# Teensy_Board_Connectors.net
KiCad netlist of a schematic drawn in EAGLE
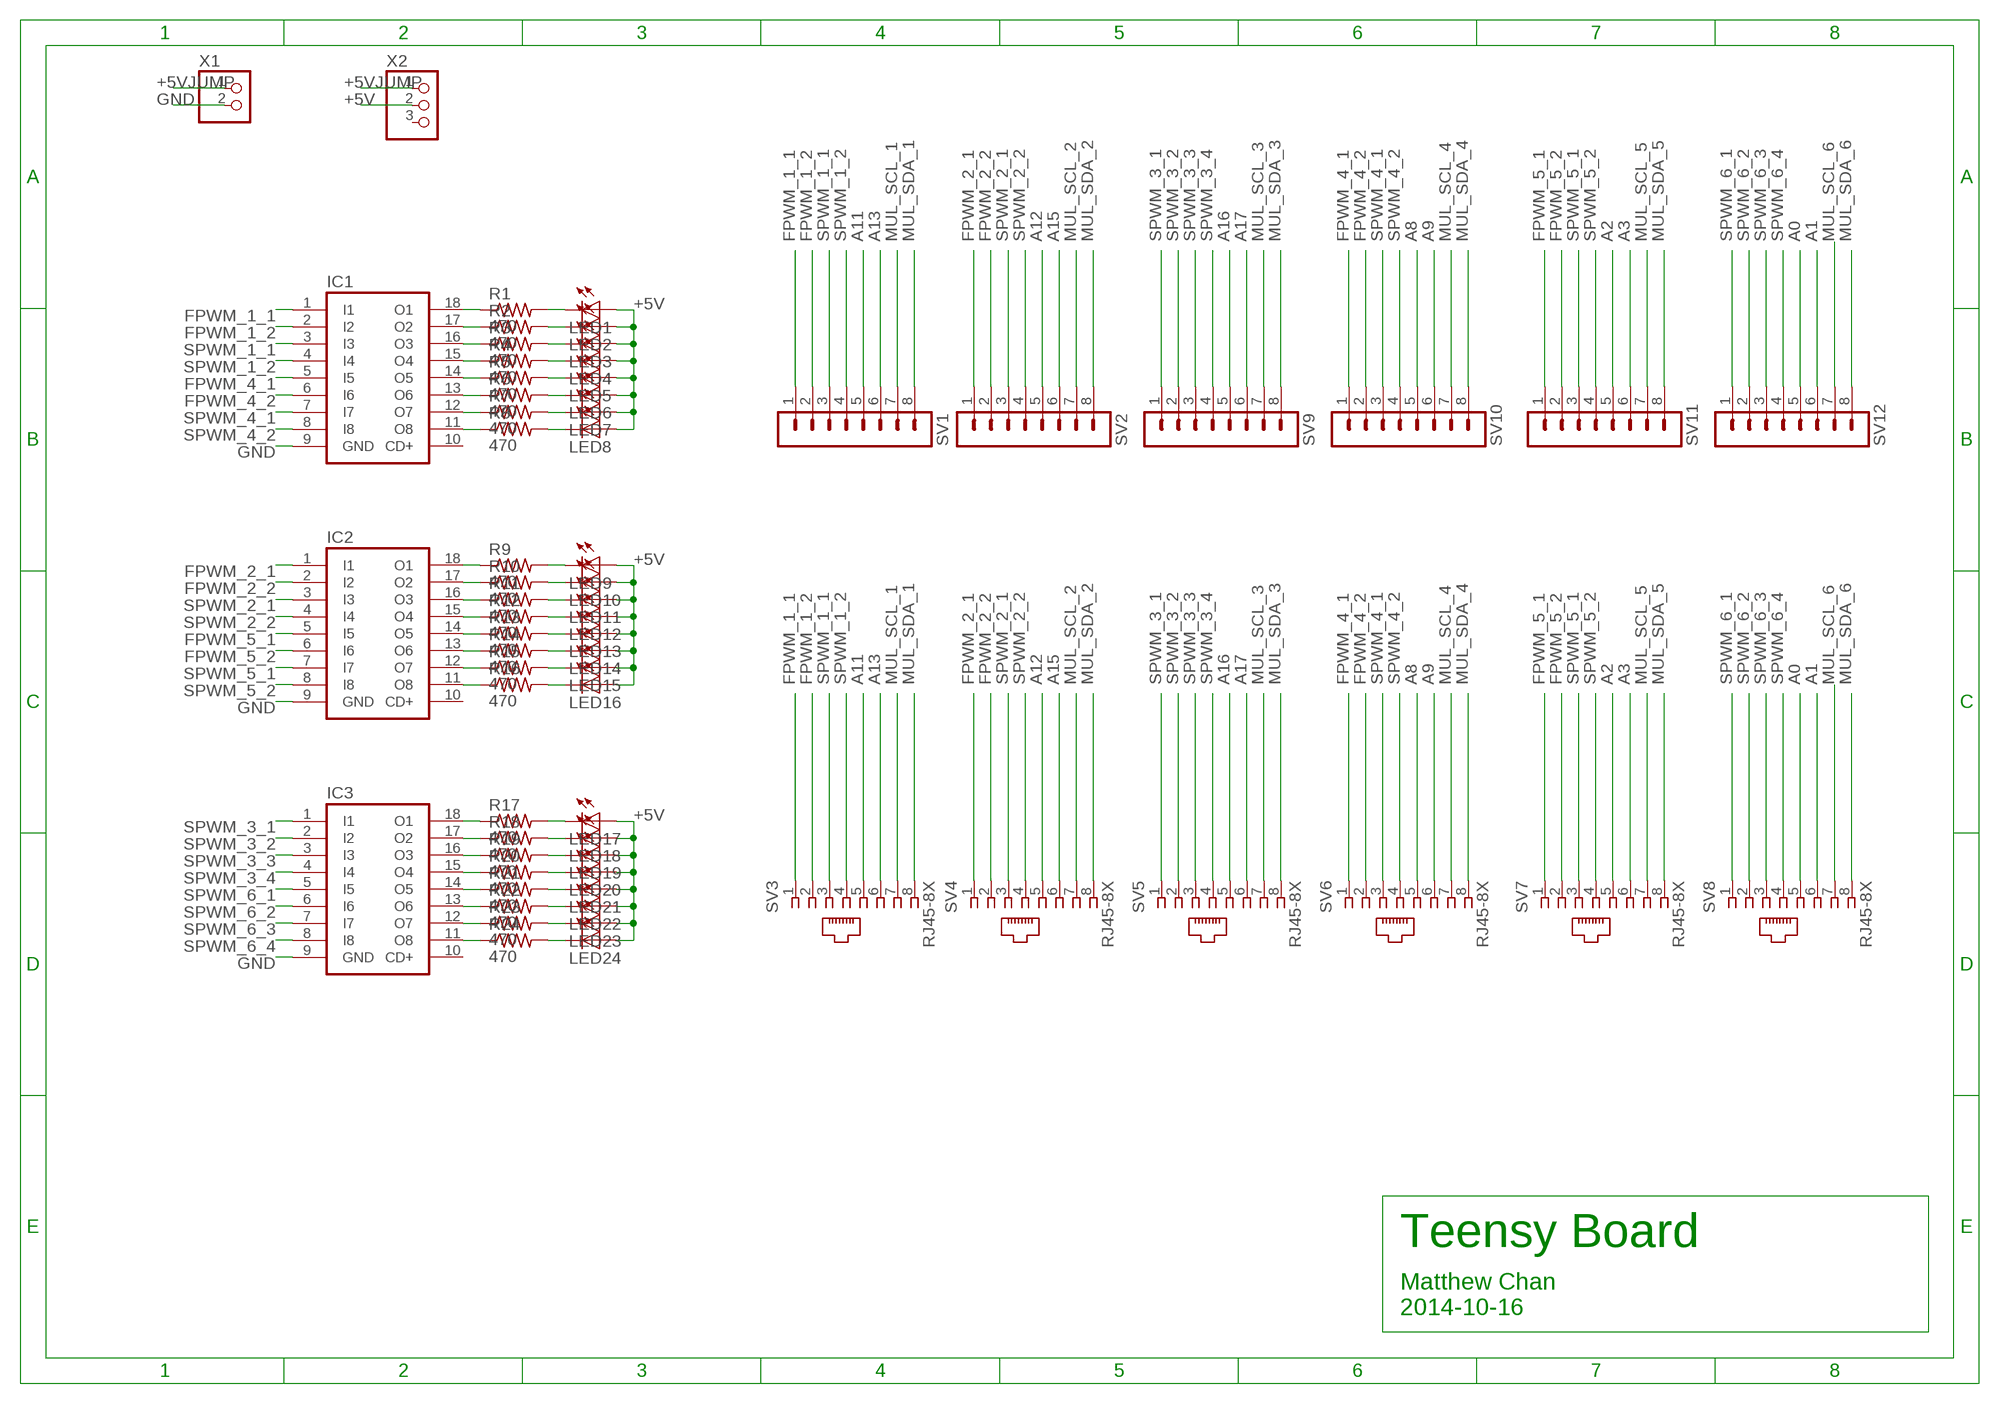
[diagram p0: schematic, sheet 1]

(export (version "E")
  (design (tool "Eeschema 10.0.6"))
  (components
    (comp (ref "IC1")
      (value "ULN2803AFWG")
      (footprint "eagle-import:SOP18")
      (libsource (lib "eagle-import") (part "ULN2803AFWG"))
    )
    (comp (ref "IC2")
      (value "ULN2803AFWG")
      (footprint "eagle-import:SOP18")
      (libsource (lib "eagle-import") (part "ULN2803AFWG"))
    )
    (comp (ref "IC3")
      (value "ULN2803AFWG")
      (footprint "eagle-import:SOP18")
      (libsource (lib "eagle-import") (part "ULN2803AFWG"))
    )
    (comp (ref "LED1")
      (value "LEDSML1206")
      (footprint "eagle-import:SML1206")
      (libsource (lib "eagle-import") (part "LEDSML1206"))
    )
    (comp (ref "LED2")
      (value "LEDSML1206")
      (footprint "eagle-import:SML1206")
      (libsource (lib "eagle-import") (part "LEDSML1206"))
    )
    (comp (ref "LED3")
      (value "LEDSML1206")
      (footprint "eagle-import:SML1206")
      (libsource (lib "eagle-import") (part "LEDSML1206"))
    )
    (comp (ref "LED4")
      (value "LEDSML1206")
      (footprint "eagle-import:SML1206")
      (libsource (lib "eagle-import") (part "LEDSML1206"))
    )
    (comp (ref "LED5")
      (value "LEDSML1206")
      (footprint "eagle-import:SML1206")
      (libsource (lib "eagle-import") (part "LEDSML1206"))
    )
    (comp (ref "LED6")
      (value "LEDSML1206")
      (footprint "eagle-import:SML1206")
      (libsource (lib "eagle-import") (part "LEDSML1206"))
    )
    (comp (ref "LED7")
      (value "LEDSML1206")
      (footprint "eagle-import:SML1206")
      (libsource (lib "eagle-import") (part "LEDSML1206"))
    )
    (comp (ref "LED8")
      (value "LEDSML1206")
      (footprint "eagle-import:SML1206")
      (libsource (lib "eagle-import") (part "LEDSML1206"))
    )
    (comp (ref "LED9")
      (value "LEDSML1206")
      (footprint "eagle-import:SML1206")
      (libsource (lib "eagle-import") (part "LEDSML1206"))
    )
    (comp (ref "LED10")
      (value "LEDSML1206")
      (footprint "eagle-import:SML1206")
      (libsource (lib "eagle-import") (part "LEDSML1206"))
    )
    (comp (ref "LED11")
      (value "LEDSML1206")
      (footprint "eagle-import:SML1206")
      (libsource (lib "eagle-import") (part "LEDSML1206"))
    )
    (comp (ref "LED12")
      (value "LEDSML1206")
      (footprint "eagle-import:SML1206")
      (libsource (lib "eagle-import") (part "LEDSML1206"))
    )
    (comp (ref "LED13")
      (value "LEDSML1206")
      (footprint "eagle-import:SML1206")
      (libsource (lib "eagle-import") (part "LEDSML1206"))
    )
    (comp (ref "LED14")
      (value "LEDSML1206")
      (footprint "eagle-import:SML1206")
      (libsource (lib "eagle-import") (part "LEDSML1206"))
    )
    (comp (ref "LED15")
      (value "LEDSML1206")
      (footprint "eagle-import:SML1206")
      (libsource (lib "eagle-import") (part "LEDSML1206"))
    )
    (comp (ref "LED16")
      (value "LEDSML1206")
      (footprint "eagle-import:SML1206")
      (libsource (lib "eagle-import") (part "LEDSML1206"))
    )
    (comp (ref "LED17")
      (value "LEDSML1206")
      (footprint "eagle-import:SML1206")
      (libsource (lib "eagle-import") (part "LEDSML1206"))
    )
    (comp (ref "LED18")
      (value "LEDSML1206")
      (footprint "eagle-import:SML1206")
      (libsource (lib "eagle-import") (part "LEDSML1206"))
    )
    (comp (ref "LED19")
      (value "LEDSML1206")
      (footprint "eagle-import:SML1206")
      (libsource (lib "eagle-import") (part "LEDSML1206"))
    )
    (comp (ref "LED20")
      (value "LEDSML1206")
      (footprint "eagle-import:SML1206")
      (libsource (lib "eagle-import") (part "LEDSML1206"))
    )
    (comp (ref "LED21")
      (value "LEDSML1206")
      (footprint "eagle-import:SML1206")
      (libsource (lib "eagle-import") (part "LEDSML1206"))
    )
    (comp (ref "LED22")
      (value "LEDSML1206")
      (footprint "eagle-import:SML1206")
      (libsource (lib "eagle-import") (part "LEDSML1206"))
    )
    (comp (ref "LED23")
      (value "LEDSML1206")
      (footprint "eagle-import:SML1206")
      (libsource (lib "eagle-import") (part "LEDSML1206"))
    )
    (comp (ref "LED24")
      (value "LEDSML1206")
      (footprint "eagle-import:SML1206")
      (libsource (lib "eagle-import") (part "LEDSML1206"))
    )
    (comp (ref "R1")
      (value "470")
      (footprint "eagle-import:R0603")
      (libsource (lib "eagle-import") (part "R-US_R0603"))
    )
    (comp (ref "R2")
      (value "470")
      (footprint "eagle-import:R0603")
      (libsource (lib "eagle-import") (part "R-US_R0603"))
    )
    (comp (ref "R3")
      (value "470")
      (footprint "eagle-import:R0603")
      (libsource (lib "eagle-import") (part "R-US_R0603"))
    )
    (comp (ref "R4")
      (value "470")
      (footprint "eagle-import:R0603")
      (libsource (lib "eagle-import") (part "R-US_R0603"))
    )
    (comp (ref "R5")
      (value "470")
      (footprint "eagle-import:R0603")
      (libsource (lib "eagle-import") (part "R-US_R0603"))
    )
    (comp (ref "R6")
      (value "470")
      (footprint "eagle-import:R0603")
      (libsource (lib "eagle-import") (part "R-US_R0603"))
    )
    (comp (ref "R7")
      (value "470")
      (footprint "eagle-import:R0603")
      (libsource (lib "eagle-import") (part "R-US_R0603"))
    )
    (comp (ref "R8")
      (value "470")
      (footprint "eagle-import:R0603")
      (libsource (lib "eagle-import") (part "R-US_R0603"))
    )
    (comp (ref "R9")
      (value "470")
      (footprint "eagle-import:R0603")
      (libsource (lib "eagle-import") (part "R-US_R0603"))
    )
    (comp (ref "R10")
      (value "470")
      (footprint "eagle-import:R0603")
      (libsource (lib "eagle-import") (part "R-US_R0603"))
    )
    (comp (ref "R11")
      (value "470")
      (footprint "eagle-import:R0603")
      (libsource (lib "eagle-import") (part "R-US_R0603"))
    )
    (comp (ref "R12")
      (value "470")
      (footprint "eagle-import:R0603")
      (libsource (lib "eagle-import") (part "R-US_R0603"))
    )
    (comp (ref "R13")
      (value "470")
      (footprint "eagle-import:R0603")
      (libsource (lib "eagle-import") (part "R-US_R0603"))
    )
    (comp (ref "R14")
      (value "470")
      (footprint "eagle-import:R0603")
      (libsource (lib "eagle-import") (part "R-US_R0603"))
    )
    (comp (ref "R15")
      (value "470")
      (footprint "eagle-import:R0603")
      (libsource (lib "eagle-import") (part "R-US_R0603"))
    )
    (comp (ref "R16")
      (value "470")
      (footprint "eagle-import:R0603")
      (libsource (lib "eagle-import") (part "R-US_R0603"))
    )
    (comp (ref "R17")
      (value "470")
      (footprint "eagle-import:R0603")
      (libsource (lib "eagle-import") (part "R-US_R0603"))
    )
    (comp (ref "R18")
      (value "470")
      (footprint "eagle-import:R0603")
      (libsource (lib "eagle-import") (part "R-US_R0603"))
    )
    (comp (ref "R19")
      (value "470")
      (footprint "eagle-import:R0603")
      (libsource (lib "eagle-import") (part "R-US_R0603"))
    )
    (comp (ref "R20")
      (value "470")
      (footprint "eagle-import:R0603")
      (libsource (lib "eagle-import") (part "R-US_R0603"))
    )
    (comp (ref "R21")
      (value "470")
      (footprint "eagle-import:R0603")
      (libsource (lib "eagle-import") (part "R-US_R0603"))
    )
    (comp (ref "R22")
      (value "470")
      (footprint "eagle-import:R0603")
      (libsource (lib "eagle-import") (part "R-US_R0603"))
    )
    (comp (ref "R23")
      (value "470")
      (footprint "eagle-import:R0603")
      (libsource (lib "eagle-import") (part "R-US_R0603"))
    )
    (comp (ref "R24")
      (value "470")
      (footprint "eagle-import:R0603")
      (libsource (lib "eagle-import") (part "R-US_R0603"))
    )
    (comp (ref "SV1")
      (value "MA08-1")
      (footprint "eagle-import:MA08-1")
      (libsource (lib "eagle-import") (part "MA08-1"))
    )
    (comp (ref "SV2")
      (value "MA08-1")
      (footprint "eagle-import:MA08-1")
      (libsource (lib "eagle-import") (part "MA08-1"))
    )
    (comp (ref "SV3")
      (value "RJ45-8X")
      (footprint "eagle-import:RJ45-NO-SHIELD")
      (libsource (lib "eagle-import") (part "RJ45-8X"))
    )
    (comp (ref "SV4")
      (value "RJ45-8X")
      (footprint "eagle-import:RJ45-NO-SHIELD")
      (libsource (lib "eagle-import") (part "RJ45-8X"))
    )
    (comp (ref "SV5")
      (value "RJ45-8X")
      (footprint "eagle-import:RJ45-NO-SHIELD")
      (libsource (lib "eagle-import") (part "RJ45-8X"))
    )
    (comp (ref "SV6")
      (value "RJ45-8X")
      (footprint "eagle-import:RJ45-NO-SHIELD")
      (libsource (lib "eagle-import") (part "RJ45-8X"))
    )
    (comp (ref "SV7")
      (value "RJ45-8X")
      (footprint "eagle-import:RJ45-NO-SHIELD")
      (libsource (lib "eagle-import") (part "RJ45-8X"))
    )
    (comp (ref "SV8")
      (value "RJ45-8X")
      (footprint "eagle-import:RJ45-NO-SHIELD")
      (libsource (lib "eagle-import") (part "RJ45-8X"))
    )
    (comp (ref "SV9")
      (value "MA08-1")
      (footprint "eagle-import:MA08-1")
      (libsource (lib "eagle-import") (part "MA08-1"))
    )
    (comp (ref "SV10")
      (value "MA08-1")
      (footprint "eagle-import:MA08-1")
      (libsource (lib "eagle-import") (part "MA08-1"))
    )
    (comp (ref "SV11")
      (value "MA08-1")
      (footprint "eagle-import:MA08-1")
      (libsource (lib "eagle-import") (part "MA08-1"))
    )
    (comp (ref "SV12")
      (value "MA08-1")
      (footprint "eagle-import:MA08-1")
      (libsource (lib "eagle-import") (part "MA08-1"))
    )
    (comp (ref "X1")
      (value "PINHD-1X2")
      (footprint "eagle-import:1X02")
      (libsource (lib "eagle-import") (part "PINHD-1X2"))
    )
    (comp (ref "X2")
      (value "PINHD-1X3")
      (footprint "eagle-import:1X03")
      (libsource (lib "eagle-import") (part "PINHD-1X3"))
    )
  )
  (nets
    (net (code "1") (name "/+5V") (class "Default")
      (node (ref "LED1") (pin "A") (pinfunction "A_A") (pintype "passive"))
      (node (ref "LED10") (pin "A") (pinfunction "A_A") (pintype "passive"))
      (node (ref "LED11") (pin "A") (pinfunction "A_A") (pintype "passive"))
      (node (ref "LED12") (pin "A") (pinfunction "A_A") (pintype "passive"))
      (node (ref "LED13") (pin "A") (pinfunction "A_A") (pintype "passive"))
      (node (ref "LED14") (pin "A") (pinfunction "A_A") (pintype "passive"))
      (node (ref "LED15") (pin "A") (pinfunction "A_A") (pintype "passive"))
      (node (ref "LED16") (pin "A") (pinfunction "A_A") (pintype "passive"))
      (node (ref "LED17") (pin "A") (pinfunction "A_A") (pintype "passive"))
      (node (ref "LED18") (pin "A") (pinfunction "A_A") (pintype "passive"))
      (node (ref "LED19") (pin "A") (pinfunction "A_A") (pintype "passive"))
      (node (ref "LED2") (pin "A") (pinfunction "A_A") (pintype "passive"))
      (node (ref "LED20") (pin "A") (pinfunction "A_A") (pintype "passive"))
      (node (ref "LED21") (pin "A") (pinfunction "A_A") (pintype "passive"))
      (node (ref "LED22") (pin "A") (pinfunction "A_A") (pintype "passive"))
      (node (ref "LED23") (pin "A") (pinfunction "A_A") (pintype "passive"))
      (node (ref "LED24") (pin "A") (pinfunction "A_A") (pintype "passive"))
      (node (ref "LED3") (pin "A") (pinfunction "A_A") (pintype "passive"))
      (node (ref "LED4") (pin "A") (pinfunction "A_A") (pintype "passive"))
      (node (ref "LED5") (pin "A") (pinfunction "A_A") (pintype "passive"))
      (node (ref "LED6") (pin "A") (pinfunction "A_A") (pintype "passive"))
      (node (ref "LED7") (pin "A") (pinfunction "A_A") (pintype "passive"))
      (node (ref "LED8") (pin "A") (pinfunction "A_A") (pintype "passive"))
      (node (ref "LED9") (pin "A") (pinfunction "A_A") (pintype "passive"))
      (node (ref "X2") (pin "2") (pinfunction "2_2") (pintype "passive"))
    )
    (net (code "2") (name "/+5VJUMP") (class "Default")
      (node (ref "X1") (pin "1") (pinfunction "1_1") (pintype "passive"))
      (node (ref "X2") (pin "1") (pinfunction "1_1") (pintype "passive"))
    )
    (net (code "3") (name "/A0") (class "Default")
      (node (ref "SV12") (pin "5") (pinfunction "5_5") (pintype "passive"))
      (node (ref "SV8") (pin "5") (pinfunction "5_5") (pintype "passive"))
    )
    (net (code "4") (name "/A1") (class "Default")
      (node (ref "SV12") (pin "6") (pinfunction "6_6") (pintype "passive"))
      (node (ref "SV8") (pin "6") (pinfunction "6_6") (pintype "passive"))
    )
    (net (code "5") (name "/A2") (class "Default")
      (node (ref "SV11") (pin "5") (pinfunction "5_5") (pintype "passive"))
      (node (ref "SV7") (pin "5") (pinfunction "5_5") (pintype "passive"))
    )
    (net (code "6") (name "/A3") (class "Default")
      (node (ref "SV11") (pin "6") (pinfunction "6_6") (pintype "passive"))
      (node (ref "SV7") (pin "6") (pinfunction "6_6") (pintype "passive"))
    )
    (net (code "7") (name "/A8") (class "Default")
      (node (ref "SV10") (pin "5") (pinfunction "5_5") (pintype "passive"))
      (node (ref "SV6") (pin "5") (pinfunction "5_5") (pintype "passive"))
    )
    (net (code "8") (name "/A9") (class "Default")
      (node (ref "SV10") (pin "6") (pinfunction "6_6") (pintype "passive"))
      (node (ref "SV6") (pin "6") (pinfunction "6_6") (pintype "passive"))
    )
    (net (code "9") (name "/A11") (class "Default")
      (node (ref "SV1") (pin "5") (pinfunction "5_5") (pintype "passive"))
      (node (ref "SV3") (pin "5") (pinfunction "5_5") (pintype "passive"))
    )
    (net (code "10") (name "/A12") (class "Default")
      (node (ref "SV2") (pin "5") (pinfunction "5_5") (pintype "passive"))
      (node (ref "SV4") (pin "5") (pinfunction "5_5") (pintype "passive"))
    )
    (net (code "11") (name "/A13") (class "Default")
      (node (ref "SV1") (pin "6") (pinfunction "6_6") (pintype "passive"))
      (node (ref "SV3") (pin "6") (pinfunction "6_6") (pintype "passive"))
    )
    (net (code "12") (name "/A15") (class "Default")
      (node (ref "SV2") (pin "6") (pinfunction "6_6") (pintype "passive"))
      (node (ref "SV4") (pin "6") (pinfunction "6_6") (pintype "passive"))
    )
    (net (code "13") (name "/A16") (class "Default")
      (node (ref "SV5") (pin "5") (pinfunction "5_5") (pintype "passive"))
      (node (ref "SV9") (pin "5") (pinfunction "5_5") (pintype "passive"))
    )
    (net (code "14") (name "/A17") (class "Default")
      (node (ref "SV5") (pin "6") (pinfunction "6_6") (pintype "passive"))
      (node (ref "SV9") (pin "6") (pinfunction "6_6") (pintype "passive"))
    )
    (net (code "15") (name "/FPWM_1_1") (class "Default")
      (node (ref "IC1") (pin "1") (pinfunction "I1_1") (pintype "input"))
      (node (ref "SV1") (pin "1") (pinfunction "1_1") (pintype "passive"))
      (node (ref "SV3") (pin "1") (pinfunction "1_1") (pintype "passive"))
    )
    (net (code "16") (name "/FPWM_1_2") (class "Default")
      (node (ref "IC1") (pin "2") (pinfunction "I2_2") (pintype "input"))
      (node (ref "SV1") (pin "2") (pinfunction "2_2") (pintype "passive"))
      (node (ref "SV3") (pin "2") (pinfunction "2_2") (pintype "passive"))
    )
    (net (code "17") (name "/FPWM_2_1") (class "Default")
      (node (ref "IC2") (pin "1") (pinfunction "I1_1") (pintype "input"))
      (node (ref "SV2") (pin "1") (pinfunction "1_1") (pintype "passive"))
      (node (ref "SV4") (pin "1") (pinfunction "1_1") (pintype "passive"))
    )
    (net (code "18") (name "/FPWM_2_2") (class "Default")
      (node (ref "IC2") (pin "2") (pinfunction "I2_2") (pintype "input"))
      (node (ref "SV2") (pin "2") (pinfunction "2_2") (pintype "passive"))
      (node (ref "SV4") (pin "2") (pinfunction "2_2") (pintype "passive"))
    )
    (net (code "19") (name "/FPWM_4_1") (class "Default")
      (node (ref "IC1") (pin "5") (pinfunction "I5_5") (pintype "input"))
      (node (ref "SV10") (pin "1") (pinfunction "1_1") (pintype "passive"))
      (node (ref "SV6") (pin "1") (pinfunction "1_1") (pintype "passive"))
    )
    (net (code "20") (name "/FPWM_4_2") (class "Default")
      (node (ref "IC1") (pin "6") (pinfunction "I6_6") (pintype "input"))
      (node (ref "SV10") (pin "2") (pinfunction "2_2") (pintype "passive"))
      (node (ref "SV6") (pin "2") (pinfunction "2_2") (pintype "passive"))
    )
    (net (code "21") (name "/FPWM_5_1") (class "Default")
      (node (ref "IC2") (pin "5") (pinfunction "I5_5") (pintype "input"))
      (node (ref "SV11") (pin "1") (pinfunction "1_1") (pintype "passive"))
      (node (ref "SV7") (pin "1") (pinfunction "1_1") (pintype "passive"))
    )
    (net (code "22") (name "/FPWM_5_2") (class "Default")
      (node (ref "IC2") (pin "6") (pinfunction "I6_6") (pintype "input"))
      (node (ref "SV11") (pin "2") (pinfunction "2_2") (pintype "passive"))
      (node (ref "SV7") (pin "2") (pinfunction "2_2") (pintype "passive"))
    )
    (net (code "23") (name "/GND") (class "Default")
      (node (ref "IC1") (pin "9") (pinfunction "GND_9") (pintype "power_in"))
      (node (ref "IC2") (pin "9") (pinfunction "GND_9") (pintype "power_in"))
      (node (ref "IC3") (pin "9") (pinfunction "GND_9") (pintype "power_in"))
      (node (ref "X1") (pin "2") (pinfunction "2_2") (pintype "passive"))
    )
    (net (code "24") (name "/MUL_SCL_1") (class "Default")
      (node (ref "SV1") (pin "7") (pinfunction "7_7") (pintype "passive"))
      (node (ref "SV3") (pin "7") (pinfunction "7_7") (pintype "passive"))
    )
    (net (code "25") (name "/MUL_SCL_2") (class "Default")
      (node (ref "SV2") (pin "7") (pinfunction "7_7") (pintype "passive"))
      (node (ref "SV4") (pin "7") (pinfunction "7_7") (pintype "passive"))
    )
    (net (code "26") (name "/MUL_SCL_3") (class "Default")
      (node (ref "SV5") (pin "7") (pinfunction "7_7") (pintype "passive"))
      (node (ref "SV9") (pin "7") (pinfunction "7_7") (pintype "passive"))
    )
    (net (code "27") (name "/MUL_SCL_4") (class "Default")
      (node (ref "SV10") (pin "7") (pinfunction "7_7") (pintype "passive"))
      (node (ref "SV6") (pin "7") (pinfunction "7_7") (pintype "passive"))
    )
    (net (code "28") (name "/MUL_SCL_5") (class "Default")
      (node (ref "SV11") (pin "7") (pinfunction "7_7") (pintype "passive"))
      (node (ref "SV7") (pin "7") (pinfunction "7_7") (pintype "passive"))
    )
    (net (code "29") (name "/MUL_SCL_6") (class "Default")
      (node (ref "SV12") (pin "7") (pinfunction "7_7") (pintype "passive"))
      (node (ref "SV8") (pin "7") (pinfunction "7_7") (pintype "passive"))
    )
    (net (code "30") (name "/MUL_SDA_1") (class "Default")
      (node (ref "SV1") (pin "8") (pinfunction "8_8") (pintype "passive"))
      (node (ref "SV3") (pin "8") (pinfunction "8_8") (pintype "passive"))
    )
    (net (code "31") (name "/MUL_SDA_2") (class "Default")
      (node (ref "SV2") (pin "8") (pinfunction "8_8") (pintype "passive"))
      (node (ref "SV4") (pin "8") (pinfunction "8_8") (pintype "passive"))
    )
    (net (code "32") (name "/MUL_SDA_3") (class "Default")
      (node (ref "SV5") (pin "8") (pinfunction "8_8") (pintype "passive"))
      (node (ref "SV9") (pin "8") (pinfunction "8_8") (pintype "passive"))
    )
    (net (code "33") (name "/MUL_SDA_4") (class "Default")
      (node (ref "SV10") (pin "8") (pinfunction "8_8") (pintype "passive"))
      (node (ref "SV6") (pin "8") (pinfunction "8_8") (pintype "passive"))
    )
    (net (code "34") (name "/MUL_SDA_5") (class "Default")
      (node (ref "SV11") (pin "8") (pinfunction "8_8") (pintype "passive"))
      (node (ref "SV7") (pin "8") (pinfunction "8_8") (pintype "passive"))
    )
    (net (code "35") (name "/MUL_SDA_6") (class "Default")
      (node (ref "SV12") (pin "8") (pinfunction "8_8") (pintype "passive"))
      (node (ref "SV8") (pin "8") (pinfunction "8_8") (pintype "passive"))
    )
    (net (code "36") (name "/SPWM_1_1") (class "Default")
      (node (ref "IC1") (pin "3") (pinfunction "I3_3") (pintype "input"))
      (node (ref "SV1") (pin "3") (pinfunction "3_3") (pintype "passive"))
      (node (ref "SV3") (pin "3") (pinfunction "3_3") (pintype "passive"))
    )
    (net (code "37") (name "/SPWM_1_2") (class "Default")
      (node (ref "IC1") (pin "4") (pinfunction "I4_4") (pintype "input"))
      (node (ref "SV1") (pin "4") (pinfunction "4_4") (pintype "passive"))
      (node (ref "SV3") (pin "4") (pinfunction "4_4") (pintype "passive"))
    )
    (net (code "38") (name "/SPWM_2_1") (class "Default")
      (node (ref "IC2") (pin "3") (pinfunction "I3_3") (pintype "input"))
      (node (ref "SV2") (pin "3") (pinfunction "3_3") (pintype "passive"))
      (node (ref "SV4") (pin "3") (pinfunction "3_3") (pintype "passive"))
    )
    (net (code "39") (name "/SPWM_2_2") (class "Default")
      (node (ref "IC2") (pin "4") (pinfunction "I4_4") (pintype "input"))
      (node (ref "SV2") (pin "4") (pinfunction "4_4") (pintype "passive"))
      (node (ref "SV4") (pin "4") (pinfunction "4_4") (pintype "passive"))
    )
    (net (code "40") (name "/SPWM_3_1") (class "Default")
      (node (ref "IC3") (pin "1") (pinfunction "I1_1") (pintype "input"))
      (node (ref "SV5") (pin "1") (pinfunction "1_1") (pintype "passive"))
      (node (ref "SV9") (pin "1") (pinfunction "1_1") (pintype "passive"))
    )
    (net (code "41") (name "/SPWM_3_2") (class "Default")
      (node (ref "IC3") (pin "2") (pinfunction "I2_2") (pintype "input"))
      (node (ref "SV5") (pin "2") (pinfunction "2_2") (pintype "passive"))
      (node (ref "SV9") (pin "2") (pinfunction "2_2") (pintype "passive"))
    )
    (net (code "42") (name "/SPWM_3_3") (class "Default")
      (node (ref "IC3") (pin "3") (pinfunction "I3_3") (pintype "input"))
      (node (ref "SV5") (pin "3") (pinfunction "3_3") (pintype "passive"))
      (node (ref "SV9") (pin "3") (pinfunction "3_3") (pintype "passive"))
    )
    (net (code "43") (name "/SPWM_3_4") (class "Default")
      (node (ref "IC3") (pin "4") (pinfunction "I4_4") (pintype "input"))
      (node (ref "SV5") (pin "4") (pinfunction "4_4") (pintype "passive"))
      (node (ref "SV9") (pin "4") (pinfunction "4_4") (pintype "passive"))
    )
    (net (code "44") (name "/SPWM_4_1") (class "Default")
      (node (ref "IC1") (pin "7") (pinfunction "I7_7") (pintype "input"))
      (node (ref "SV10") (pin "3") (pinfunction "3_3") (pintype "passive"))
      (node (ref "SV6") (pin "3") (pinfunction "3_3") (pintype "passive"))
    )
    (net (code "45") (name "/SPWM_4_2") (class "Default")
      (node (ref "IC1") (pin "8") (pinfunction "I8_8") (pintype "input"))
      (node (ref "SV10") (pin "4") (pinfunction "4_4") (pintype "passive"))
      (node (ref "SV6") (pin "4") (pinfunction "4_4") (pintype "passive"))
    )
    (net (code "46") (name "/SPWM_5_1") (class "Default")
      (node (ref "IC2") (pin "7") (pinfunction "I7_7") (pintype "input"))
      (node (ref "SV11") (pin "3") (pinfunction "3_3") (pintype "passive"))
      (node (ref "SV7") (pin "3") (pinfunction "3_3") (pintype "passive"))
    )
    (net (code "47") (name "/SPWM_5_2") (class "Default")
      (node (ref "IC2") (pin "8") (pinfunction "I8_8") (pintype "input"))
      (node (ref "SV11") (pin "4") (pinfunction "4_4") (pintype "passive"))
      (node (ref "SV7") (pin "4") (pinfunction "4_4") (pintype "passive"))
    )
    (net (code "48") (name "/SPWM_6_1") (class "Default")
      (node (ref "IC3") (pin "5") (pinfunction "I5_5") (pintype "input"))
      (node (ref "SV12") (pin "1") (pinfunction "1_1") (pintype "passive"))
      (node (ref "SV8") (pin "1") (pinfunction "1_1") (pintype "passive"))
    )
    (net (code "49") (name "/SPWM_6_2") (class "Default")
      (node (ref "IC3") (pin "6") (pinfunction "I6_6") (pintype "input"))
      (node (ref "SV12") (pin "2") (pinfunction "2_2") (pintype "passive"))
      (node (ref "SV8") (pin "2") (pinfunction "2_2") (pintype "passive"))
    )
    (net (code "50") (name "/SPWM_6_3") (class "Default")
      (node (ref "IC3") (pin "7") (pinfunction "I7_7") (pintype "input"))
      (node (ref "SV12") (pin "3") (pinfunction "3_3") (pintype "passive"))
      (node (ref "SV8") (pin "3") (pinfunction "3_3") (pintype "passive"))
    )
    (net (code "51") (name "/SPWM_6_4") (class "Default")
      (node (ref "IC3") (pin "8") (pinfunction "I8_8") (pintype "input"))
      (node (ref "SV12") (pin "4") (pinfunction "4_4") (pintype "passive"))
      (node (ref "SV8") (pin "4") (pinfunction "4_4") (pintype "passive"))
    )
    (net (code "52") (name "Net-(IC1-O1)") (class "Default")
      (node (ref "IC1") (pin "18") (pinfunction "O1_18") (pintype "open_collector"))
      (node (ref "R1") (pin "1") (pinfunction "1_1") (pintype "passive"))
    )
    (net (code "53") (name "Net-(IC1-O2)") (class "Default")
      (node (ref "IC1") (pin "17") (pinfunction "O2_17") (pintype "open_collector"))
      (node (ref "R2") (pin "1") (pinfunction "1_1") (pintype "passive"))
    )
    (net (code "54") (name "Net-(IC1-O3)") (class "Default")
      (node (ref "IC1") (pin "16") (pinfunction "O3_16") (pintype "open_collector"))
      (node (ref "R3") (pin "1") (pinfunction "1_1") (pintype "passive"))
    )
    (net (code "55") (name "Net-(IC1-O4)") (class "Default")
      (node (ref "IC1") (pin "15") (pinfunction "O4_15") (pintype "open_collector"))
      (node (ref "R4") (pin "1") (pinfunction "1_1") (pintype "passive"))
    )
    (net (code "56") (name "Net-(IC1-O5)") (class "Default")
      (node (ref "IC1") (pin "14") (pinfunction "O5_14") (pintype "open_collector"))
      (node (ref "R5") (pin "1") (pinfunction "1_1") (pintype "passive"))
    )
    (net (code "57") (name "Net-(IC1-O6)") (class "Default")
      (node (ref "IC1") (pin "13") (pinfunction "O6_13") (pintype "open_collector"))
      (node (ref "R6") (pin "1") (pinfunction "1_1") (pintype "passive"))
    )
    (net (code "58") (name "Net-(IC1-O7)") (class "Default")
      (node (ref "IC1") (pin "12") (pinfunction "O7_12") (pintype "open_collector"))
      (node (ref "R7") (pin "1") (pinfunction "1_1") (pintype "passive"))
    )
    (net (code "59") (name "Net-(IC1-O8)") (class "Default")
      (node (ref "IC1") (pin "11") (pinfunction "O8_11") (pintype "open_collector"))
      (node (ref "R8") (pin "1") (pinfunction "1_1") (pintype "passive"))
    )
    (net (code "60") (name "Net-(IC2-O1)") (class "Default")
      (node (ref "IC2") (pin "18") (pinfunction "O1_18") (pintype "open_collector"))
      (node (ref "R9") (pin "1") (pinfunction "1_1") (pintype "passive"))
    )
    (net (code "61") (name "Net-(IC2-O2)") (class "Default")
      (node (ref "IC2") (pin "17") (pinfunction "O2_17") (pintype "open_collector"))
      (node (ref "R10") (pin "1") (pinfunction "1_1") (pintype "passive"))
    )
    (net (code "62") (name "Net-(IC2-O3)") (class "Default")
      (node (ref "IC2") (pin "16") (pinfunction "O3_16") (pintype "open_collector"))
      (node (ref "R11") (pin "1") (pinfunction "1_1") (pintype "passive"))
    )
    (net (code "63") (name "Net-(IC2-O4)") (class "Default")
      (node (ref "IC2") (pin "15") (pinfunction "O4_15") (pintype "open_collector"))
      (node (ref "R12") (pin "1") (pinfunction "1_1") (pintype "passive"))
    )
    (net (code "64") (name "Net-(IC2-O5)") (class "Default")
      (node (ref "IC2") (pin "14") (pinfunction "O5_14") (pintype "open_collector"))
      (node (ref "R13") (pin "1") (pinfunction "1_1") (pintype "passive"))
    )
    (net (code "65") (name "Net-(IC2-O6)") (class "Default")
      (node (ref "IC2") (pin "13") (pinfunction "O6_13") (pintype "open_collector"))
      (node (ref "R14") (pin "1") (pinfunction "1_1") (pintype "passive"))
    )
    (net (code "66") (name "Net-(IC2-O7)") (class "Default")
      (node (ref "IC2") (pin "12") (pinfunction "O7_12") (pintype "open_collector"))
      (node (ref "R15") (pin "1") (pinfunction "1_1") (pintype "passive"))
    )
    (net (code "67") (name "Net-(IC2-O8)") (class "Default")
      (node (ref "IC2") (pin "11") (pinfunction "O8_11") (pintype "open_collector"))
      (node (ref "R16") (pin "1") (pinfunction "1_1") (pintype "passive"))
    )
    (net (code "68") (name "Net-(IC3-O1)") (class "Default")
      (node (ref "IC3") (pin "18") (pinfunction "O1_18") (pintype "open_collector"))
      (node (ref "R17") (pin "1") (pinfunction "1_1") (pintype "passive"))
    )
    (net (code "69") (name "Net-(IC3-O2)") (class "Default")
      (node (ref "IC3") (pin "17") (pinfunction "O2_17") (pintype "open_collector"))
      (node (ref "R18") (pin "1") (pinfunction "1_1") (pintype "passive"))
    )
    (net (code "70") (name "Net-(IC3-O3)") (class "Default")
      (node (ref "IC3") (pin "16") (pinfunction "O3_16") (pintype "open_collector"))
      (node (ref "R19") (pin "1") (pinfunction "1_1") (pintype "passive"))
    )
    (net (code "71") (name "Net-(IC3-O4)") (class "Default")
      (node (ref "IC3") (pin "15") (pinfunction "O4_15") (pintype "open_collector"))
      (node (ref "R20") (pin "1") (pinfunction "1_1") (pintype "passive"))
    )
    (net (code "72") (name "Net-(IC3-O5)") (class "Default")
      (node (ref "IC3") (pin "14") (pinfunction "O5_14") (pintype "open_collector"))
      (node (ref "R21") (pin "1") (pinfunction "1_1") (pintype "passive"))
    )
    (net (code "73") (name "Net-(IC3-O6)") (class "Default")
      (node (ref "IC3") (pin "13") (pinfunction "O6_13") (pintype "open_collector"))
      (node (ref "R22") (pin "1") (pinfunction "1_1") (pintype "passive"))
    )
    (net (code "74") (name "Net-(IC3-O7)") (class "Default")
      (node (ref "IC3") (pin "12") (pinfunction "O7_12") (pintype "open_collector"))
      (node (ref "R23") (pin "1") (pinfunction "1_1") (pintype "passive"))
    )
    (net (code "75") (name "Net-(IC3-O8)") (class "Default")
      (node (ref "IC3") (pin "11") (pinfunction "O8_11") (pintype "open_collector"))
      (node (ref "R24") (pin "1") (pinfunction "1_1") (pintype "passive"))
    )
    (net (code "76") (name "Net-(LED1-PadC)") (class "Default")
      (node (ref "LED1") (pin "C") (pinfunction "C_C") (pintype "passive"))
      (node (ref "R1") (pin "2") (pinfunction "2_2") (pintype "passive"))
    )
    (net (code "77") (name "Net-(LED2-PadC)") (class "Default")
      (node (ref "LED2") (pin "C") (pinfunction "C_C") (pintype "passive"))
      (node (ref "R2") (pin "2") (pinfunction "2_2") (pintype "passive"))
    )
    (net (code "78") (name "Net-(LED3-PadC)") (class "Default")
      (node (ref "LED3") (pin "C") (pinfunction "C_C") (pintype "passive"))
      (node (ref "R3") (pin "2") (pinfunction "2_2") (pintype "passive"))
    )
    (net (code "79") (name "Net-(LED4-PadC)") (class "Default")
      (node (ref "LED4") (pin "C") (pinfunction "C_C") (pintype "passive"))
      (node (ref "R4") (pin "2") (pinfunction "2_2") (pintype "passive"))
    )
    (net (code "80") (name "Net-(LED5-PadC)") (class "Default")
      (node (ref "LED5") (pin "C") (pinfunction "C_C") (pintype "passive"))
      (node (ref "R5") (pin "2") (pinfunction "2_2") (pintype "passive"))
    )
    (net (code "81") (name "Net-(LED6-PadC)") (class "Default")
      (node (ref "LED6") (pin "C") (pinfunction "C_C") (pintype "passive"))
      (node (ref "R6") (pin "2") (pinfunction "2_2") (pintype "passive"))
    )
    (net (code "82") (name "Net-(LED7-PadC)") (class "Default")
      (node (ref "LED7") (pin "C") (pinfunction "C_C") (pintype "passive"))
      (node (ref "R7") (pin "2") (pinfunction "2_2") (pintype "passive"))
    )
    (net (code "83") (name "Net-(LED8-PadC)") (class "Default")
      (node (ref "LED8") (pin "C") (pinfunction "C_C") (pintype "passive"))
      (node (ref "R8") (pin "2") (pinfunction "2_2") (pintype "passive"))
    )
    (net (code "84") (name "Net-(LED9-PadC)") (class "Default")
      (node (ref "LED9") (pin "C") (pinfunction "C_C") (pintype "passive"))
      (node (ref "R9") (pin "2") (pinfunction "2_2") (pintype "passive"))
    )
    (net (code "85") (name "Net-(LED10-PadC)") (class "Default")
      (node (ref "LED10") (pin "C") (pinfunction "C_C") (pintype "passive"))
      (node (ref "R10") (pin "2") (pinfunction "2_2") (pintype "passive"))
    )
    (net (code "86") (name "Net-(LED11-PadC)") (class "Default")
      (node (ref "LED11") (pin "C") (pinfunction "C_C") (pintype "passive"))
      (node (ref "R11") (pin "2") (pinfunction "2_2") (pintype "passive"))
    )
    (net (code "87") (name "Net-(LED12-PadC)") (class "Default")
      (node (ref "LED12") (pin "C") (pinfunction "C_C") (pintype "passive"))
      (node (ref "R12") (pin "2") (pinfunction "2_2") (pintype "passive"))
    )
    (net (code "88") (name "Net-(LED13-PadC)") (class "Default")
      (node (ref "LED13") (pin "C") (pinfunction "C_C") (pintype "passive"))
      (node (ref "R13") (pin "2") (pinfunction "2_2") (pintype "passive"))
    )
    (net (code "89") (name "Net-(LED14-PadC)") (class "Default")
      (node (ref "LED14") (pin "C") (pinfunction "C_C") (pintype "passive"))
      (node (ref "R14") (pin "2") (pinfunction "2_2") (pintype "passive"))
    )
    (net (code "90") (name "Net-(LED15-PadC)") (class "Default")
      (node (ref "LED15") (pin "C") (pinfunction "C_C") (pintype "passive"))
      (node (ref "R15") (pin "2") (pinfunction "2_2") (pintype "passive"))
    )
    (net (code "91") (name "Net-(LED16-PadC)") (class "Default")
      (node (ref "LED16") (pin "C") (pinfunction "C_C") (pintype "passive"))
      (node (ref "R16") (pin "2") (pinfunction "2_2") (pintype "passive"))
    )
    (net (code "92") (name "Net-(LED17-PadC)") (class "Default")
      (node (ref "LED17") (pin "C") (pinfunction "C_C") (pintype "passive"))
      (node (ref "R17") (pin "2") (pinfunction "2_2") (pintype "passive"))
    )
    (net (code "93") (name "Net-(LED18-PadC)") (class "Default")
      (node (ref "LED18") (pin "C") (pinfunction "C_C") (pintype "passive"))
      (node (ref "R18") (pin "2") (pinfunction "2_2") (pintype "passive"))
    )
    (net (code "94") (name "Net-(LED19-PadC)") (class "Default")
      (node (ref "LED19") (pin "C") (pinfunction "C_C") (pintype "passive"))
      (node (ref "R19") (pin "2") (pinfunction "2_2") (pintype "passive"))
    )
    (net (code "95") (name "Net-(LED20-PadC)") (class "Default")
      (node (ref "LED20") (pin "C") (pinfunction "C_C") (pintype "passive"))
      (node (ref "R20") (pin "2") (pinfunction "2_2") (pintype "passive"))
    )
    (net (code "96") (name "Net-(LED21-PadC)") (class "Default")
      (node (ref "LED21") (pin "C") (pinfunction "C_C") (pintype "passive"))
      (node (ref "R21") (pin "2") (pinfunction "2_2") (pintype "passive"))
    )
    (net (code "97") (name "Net-(LED22-PadC)") (class "Default")
      (node (ref "LED22") (pin "C") (pinfunction "C_C") (pintype "passive"))
      (node (ref "R22") (pin "2") (pinfunction "2_2") (pintype "passive"))
    )
    (net (code "98") (name "Net-(LED23-PadC)") (class "Default")
      (node (ref "LED23") (pin "C") (pinfunction "C_C") (pintype "passive"))
      (node (ref "R23") (pin "2") (pinfunction "2_2") (pintype "passive"))
    )
    (net (code "99") (name "Net-(LED24-PadC)") (class "Default")
      (node (ref "LED24") (pin "C") (pinfunction "C_C") (pintype "passive"))
      (node (ref "R24") (pin "2") (pinfunction "2_2") (pintype "passive"))
    )
    (net (code "100") (name "unconnected-(IC1-CD+-Pad10)") (class "Default")
      (node (ref "IC1") (pin "10") (pinfunction "CD+_10") (pintype "passive"))
    )
    (net (code "101") (name "unconnected-(IC2-CD+-Pad10)") (class "Default")
      (node (ref "IC2") (pin "10") (pinfunction "CD+_10") (pintype "passive"))
    )
    (net (code "102") (name "unconnected-(IC3-CD+-Pad10)") (class "Default")
      (node (ref "IC3") (pin "10") (pinfunction "CD+_10") (pintype "passive"))
    )
    (net (code "103") (name "unconnected-(X2-Pad3)") (class "Default")
      (node (ref "X2") (pin "3") (pinfunction "3_3") (pintype "passive"))
    )
  )
)
